# bottomboard.net
KiCad netlist of a schematic drawn in EAGLE
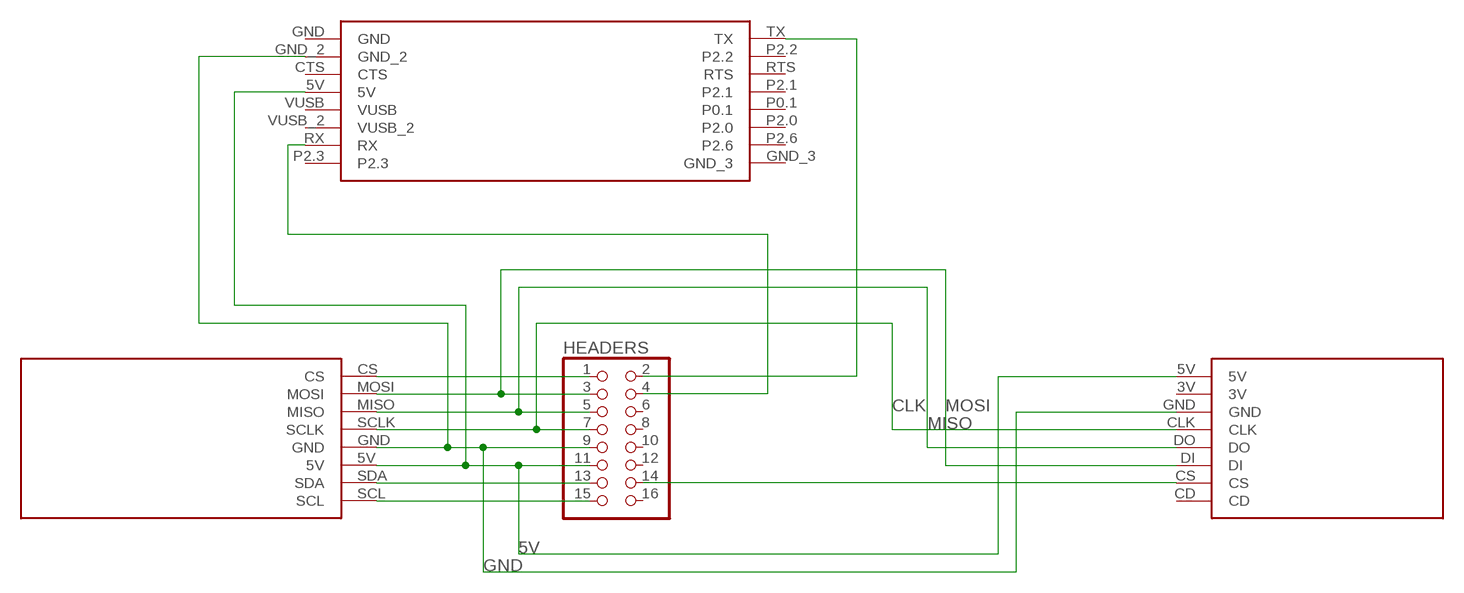
[diagram p0: schematic, sheet 1]

(export (version "E")
  (design (tool "Eeschema 10.0.6"))
  (components
    (comp (ref "HEADERS")
      (value "PINHD-2X8")
      (footprint "eagle-import:2X08")
      (libsource (lib "eagle-import") (part "PINHD-2X8"))
    )
    (comp (ref "U$1")
      (value "COMMS")
      (footprint "eagle-import:COMMS")
      (libsource (lib "eagle-import") (part "COMMS"))
    )
    (comp (ref "U$2")
      (value "SDCARD")
      (footprint "eagle-import:SDCARD")
      (libsource (lib "eagle-import") (part "SDCARD"))
    )
    (comp (ref "U$3")
      (value "ARDUCAM")
      (footprint "eagle-import:ARDUCAM")
      (libsource (lib "eagle-import") (part "ARDUCAM"))
    )
  )
  (nets
    (net (code "1") (name "/5V") (class "Default")
      (node (ref "HEADERS") (pin "11") (pinfunction "11_11") (pintype "passive"))
      (node (ref "U$1") (pin "5V") (pinfunction "5V_5V") (pintype "bidirectional"))
      (node (ref "U$2") (pin "5V") (pinfunction "5V_5V") (pintype "bidirectional"))
      (node (ref "U$3") (pin "5V") (pinfunction "5V_5V") (pintype "bidirectional"))
    )
    (net (code "2") (name "/CLK") (class "Default")
      (node (ref "HEADERS") (pin "7") (pinfunction "7_7") (pintype "passive"))
      (node (ref "U$2") (pin "CLK") (pinfunction "CLK_CLK") (pintype "bidirectional"))
      (node (ref "U$3") (pin "SCLK") (pinfunction "SCLK_SCLK") (pintype "bidirectional"))
    )
    (net (code "3") (name "/GND") (class "Default")
      (node (ref "HEADERS") (pin "9") (pinfunction "9_9") (pintype "passive"))
      (node (ref "U$1") (pin "GND_2") (pinfunction "GND_2_GND_2") (pintype "bidirectional"))
      (node (ref "U$2") (pin "GND") (pinfunction "GND_GND") (pintype "bidirectional"))
      (node (ref "U$3") (pin "GND") (pinfunction "GND_GND") (pintype "bidirectional"))
    )
    (net (code "4") (name "/MISO") (class "Default")
      (node (ref "HEADERS") (pin "5") (pinfunction "5_5") (pintype "passive"))
      (node (ref "U$2") (pin "DO") (pinfunction "DO_DO") (pintype "bidirectional"))
      (node (ref "U$3") (pin "MISO") (pinfunction "MISO_MISO") (pintype "bidirectional"))
    )
    (net (code "5") (name "/MOSI") (class "Default")
      (node (ref "HEADERS") (pin "3") (pinfunction "3_3") (pintype "passive"))
      (node (ref "U$2") (pin "DI") (pinfunction "DI_DI") (pintype "bidirectional"))
      (node (ref "U$3") (pin "MOSI") (pinfunction "MOSI_MOSI") (pintype "bidirectional"))
    )
    (net (code "6") (name "Net-(HEADERS-Pad1)") (class "Default")
      (node (ref "HEADERS") (pin "1") (pinfunction "1_1") (pintype "passive"))
      (node (ref "U$3") (pin "CS") (pinfunction "CS_CS") (pintype "bidirectional"))
    )
    (net (code "7") (name "Net-(HEADERS-Pad2)") (class "Default")
      (node (ref "HEADERS") (pin "2") (pinfunction "2_2") (pintype "passive"))
      (node (ref "U$1") (pin "TX") (pinfunction "TX_TX") (pintype "bidirectional"))
    )
    (net (code "8") (name "Net-(HEADERS-Pad4)") (class "Default")
      (node (ref "HEADERS") (pin "4") (pinfunction "4_4") (pintype "passive"))
      (node (ref "U$1") (pin "RX") (pinfunction "RX_RX") (pintype "bidirectional"))
    )
    (net (code "9") (name "Net-(HEADERS-Pad13)") (class "Default")
      (node (ref "HEADERS") (pin "13") (pinfunction "13_13") (pintype "passive"))
      (node (ref "U$3") (pin "SDA") (pinfunction "SDA_SDA") (pintype "bidirectional"))
    )
    (net (code "10") (name "Net-(HEADERS-Pad14)") (class "Default")
      (node (ref "HEADERS") (pin "14") (pinfunction "14_14") (pintype "passive"))
      (node (ref "U$2") (pin "CS") (pinfunction "CS_CS") (pintype "bidirectional"))
    )
    (net (code "11") (name "Net-(HEADERS-Pad15)") (class "Default")
      (node (ref "HEADERS") (pin "15") (pinfunction "15_15") (pintype "passive"))
      (node (ref "U$3") (pin "SCL") (pinfunction "SCL_SCL") (pintype "bidirectional"))
    )
    (net (code "12") (name "unconnected-(HEADERS-Pad6)") (class "Default")
      (node (ref "HEADERS") (pin "6") (pinfunction "6_6") (pintype "passive"))
    )
    (net (code "13") (name "unconnected-(HEADERS-Pad8)") (class "Default")
      (node (ref "HEADERS") (pin "8") (pinfunction "8_8") (pintype "passive"))
    )
    (net (code "14") (name "unconnected-(HEADERS-Pad10)") (class "Default")
      (node (ref "HEADERS") (pin "10") (pinfunction "10_10") (pintype "passive"))
    )
    (net (code "15") (name "unconnected-(HEADERS-Pad12)") (class "Default")
      (node (ref "HEADERS") (pin "12") (pinfunction "12_12") (pintype "passive"))
    )
    (net (code "16") (name "unconnected-(HEADERS-Pad16)") (class "Default")
      (node (ref "HEADERS") (pin "16") (pinfunction "16_16") (pintype "passive"))
    )
    (net (code "17") (name "unconnected-(U$1-PadCTS)") (class "Default")
      (node (ref "U$1") (pin "CTS") (pinfunction "CTS_CTS") (pintype "bidirectional"))
    )
    (net (code "18") (name "unconnected-(U$1-PadGND)") (class "Default")
      (node (ref "U$1") (pin "GND") (pinfunction "GND_GND") (pintype "bidirectional"))
    )
    (net (code "19") (name "unconnected-(U$1-PadGND_3)") (class "Default")
      (node (ref "U$1") (pin "GND_3") (pinfunction "GND_3_GND_3") (pintype "bidirectional"))
    )
    (net (code "20") (name "unconnected-(U$1-PadP0.1)") (class "Default")
      (node (ref "U$1") (pin "P0.1") (pinfunction "P0.1_P0.1") (pintype "bidirectional"))
    )
    (net (code "21") (name "unconnected-(U$1-PadP2.0)") (class "Default")
      (node (ref "U$1") (pin "P2.0") (pinfunction "P2.0_P2.0") (pintype "bidirectional"))
    )
    (net (code "22") (name "unconnected-(U$1-PadP2.1)") (class "Default")
      (node (ref "U$1") (pin "P2.1") (pinfunction "P2.1_P2.1") (pintype "bidirectional"))
    )
    (net (code "23") (name "unconnected-(U$1-PadP2.2)") (class "Default")
      (node (ref "U$1") (pin "P2.2") (pinfunction "P2.2_P2.2") (pintype "bidirectional"))
    )
    (net (code "24") (name "unconnected-(U$1-PadP2.3)") (class "Default")
      (node (ref "U$1") (pin "P2.3") (pinfunction "P2.3_P2.3") (pintype "bidirectional"))
    )
    (net (code "25") (name "unconnected-(U$1-PadP2.6)") (class "Default")
      (node (ref "U$1") (pin "P2.6") (pinfunction "P2.6_P2.6") (pintype "bidirectional"))
    )
    (net (code "26") (name "unconnected-(U$1-PadRTS)") (class "Default")
      (node (ref "U$1") (pin "RTS") (pinfunction "RTS_RTS") (pintype "bidirectional"))
    )
    (net (code "27") (name "unconnected-(U$1-PadVUSB)") (class "Default")
      (node (ref "U$1") (pin "VUSB") (pinfunction "VUSB_VUSB") (pintype "bidirectional"))
    )
    (net (code "28") (name "unconnected-(U$1-PadVUSB_2)") (class "Default")
      (node (ref "U$1") (pin "VUSB_2") (pinfunction "VUSB_2_VUSB_2") (pintype "bidirectional"))
    )
    (net (code "29") (name "unconnected-(U$2-Pad3V)") (class "Default")
      (node (ref "U$2") (pin "3V") (pinfunction "3V_3V") (pintype "bidirectional"))
    )
    (net (code "30") (name "unconnected-(U$2-PadCD)") (class "Default")
      (node (ref "U$2") (pin "CD") (pinfunction "CD_CD") (pintype "bidirectional"))
    )
  )
)
